# mc-v1-sch.net
KiCad netlist of a schematic drawn in EAGLE
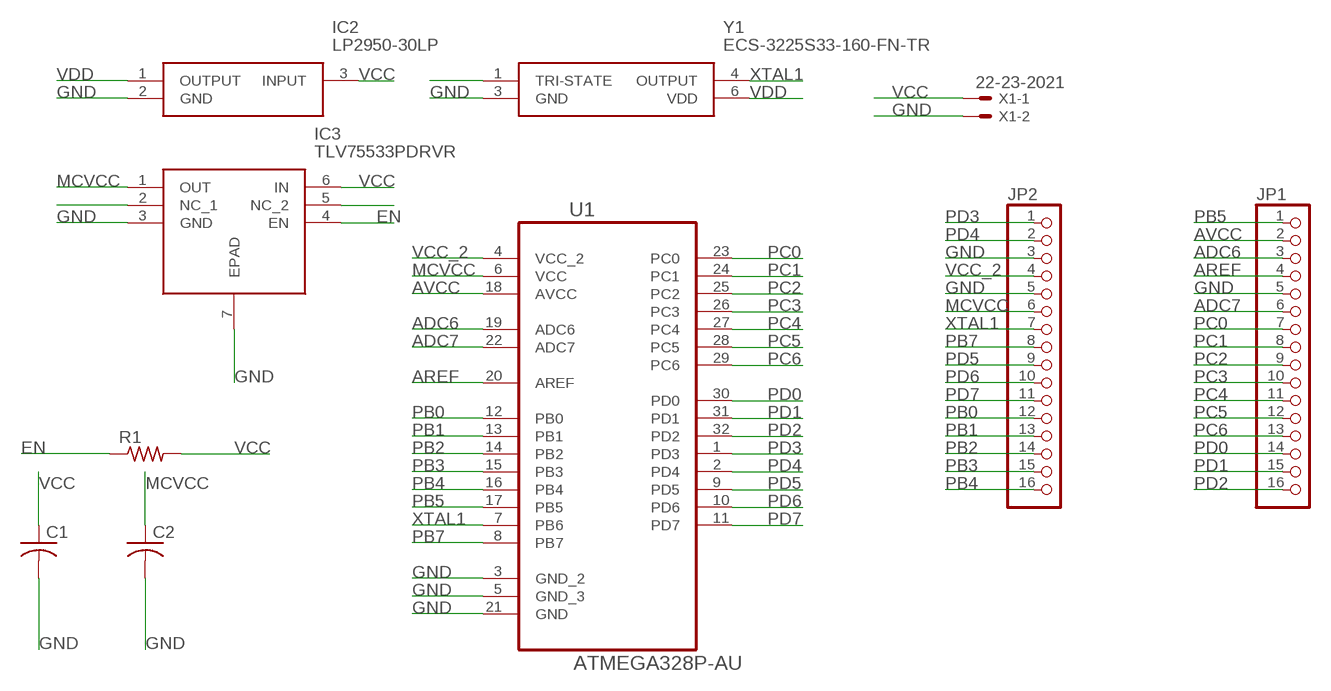
[diagram p0: schematic, sheet 1]

(export (version "E")
  (design (tool "Eeschema 10.0.6"))
  (components
    (comp (ref "C1")
      (value "C-USC1206")
      (footprint "eagle-import:C1206")
      (libsource (lib "eagle-import") (part "C-USC1206"))
    )
    (comp (ref "C2")
      (value "C-USC1206")
      (footprint "eagle-import:C1206")
      (libsource (lib "eagle-import") (part "C-USC1206"))
    )
    (comp (ref "IC2")
      (value "LP2950-30LP")
      (footprint "eagle-import:LP0003A")
      (fields (field (name "MOUSER_PART_NUMBER") "595-LP2950-30LP") (field (name "RS_PART_NUMBER") "7620437"))
      (libsource (lib "eagle-import") (part "LP2950-30LP"))
    )
    (comp (ref "IC3")
      (value "TLV75533PDRVR")
      (footprint "eagle-import:SON65P200X200X80-7N")
      (fields (field (name "MOUSER_PART_NUMBER") "595-TLV75533PDRVR"))
      (libsource (lib "eagle-import") (part "TLV75533PDRVR"))
    )
    (comp (ref "JP1")
      (value "PINHD-1X16")
      (footprint "eagle-import:1X16")
      (libsource (lib "eagle-import") (part "PINHD-1X16"))
    )
    (comp (ref "JP2")
      (value "PINHD-1X16")
      (footprint "eagle-import:1X16")
      (libsource (lib "eagle-import") (part "PINHD-1X16"))
    )
    (comp (ref "R1")
      (value "R-US_R0603")
      (footprint "eagle-import:R0603")
      (libsource (lib "eagle-import") (part "R-US_R0603"))
    )
    (comp (ref "U1")
      (value "ATMEGA328P-AU")
      (footprint "eagle-import:QFP80P900X900X120-32N")
      (libsource (lib "eagle-import") (part "ATMEGA328P-AU"))
    )
    (comp (ref "X1")
      (value "22-23-2021")
      (footprint "eagle-import:22-23-2021")
      (fields (field (name "MF") "MOLEX"))
      (libsource (lib "eagle-import") (part "22-23-2021"))
    )
    (comp (ref "Y1")
      (value "ECS-3225S33-160-FN-TR")
      (footprint "eagle-import:ECS3225S33200FNTR")
      (fields (field (name "MOUSER_PART_NUMBER") "520-3225S33-160-FNT"))
      (libsource (lib "eagle-import") (part "ECS-3225S33-160-FN-TR"))
    )
  )
  (nets
    (net (code "1") (name "/ADC6") (class "Default")
      (node (ref "JP1") (pin "3") (pinfunction "3_3") (pintype "passive"))
      (node (ref "U1") (pin "19") (pinfunction "ADC6_19") (pintype "input"))
    )
    (net (code "2") (name "/ADC7") (class "Default")
      (node (ref "JP1") (pin "6") (pinfunction "6_6") (pintype "passive"))
      (node (ref "U1") (pin "22") (pinfunction "ADC7_22") (pintype "input"))
    )
    (net (code "3") (name "/AREF") (class "Default")
      (node (ref "JP1") (pin "4") (pinfunction "4_4") (pintype "passive"))
      (node (ref "U1") (pin "20") (pinfunction "AREF_20") (pintype "input"))
    )
    (net (code "4") (name "/AVCC") (class "Default")
      (node (ref "JP1") (pin "2") (pinfunction "2_2") (pintype "passive"))
      (node (ref "U1") (pin "18") (pinfunction "AVCC_18") (pintype "power_in"))
    )
    (net (code "5") (name "/EN") (class "Default")
      (node (ref "IC3") (pin "4") (pinfunction "EN_4") (pintype "bidirectional"))
      (node (ref "R1") (pin "1") (pinfunction "1_1") (pintype "passive"))
    )
    (net (code "6") (name "/GND") (class "Default")
      (node (ref "C1") (pin "2") (pinfunction "2_2") (pintype "passive"))
      (node (ref "C2") (pin "2") (pinfunction "2_2") (pintype "passive"))
      (node (ref "IC2") (pin "2") (pinfunction "GND_2") (pintype "bidirectional"))
      (node (ref "IC3") (pin "3") (pinfunction "GND_3") (pintype "bidirectional"))
      (node (ref "IC3") (pin "7") (pinfunction "EPAD_7") (pintype "bidirectional"))
      (node (ref "JP1") (pin "5") (pinfunction "5_5") (pintype "passive"))
      (node (ref "JP2") (pin "3") (pinfunction "3_3") (pintype "passive"))
      (node (ref "JP2") (pin "5") (pinfunction "5_5") (pintype "passive"))
      (node (ref "U1") (pin "21") (pinfunction "GND_21") (pintype "passive"))
      (node (ref "U1") (pin "3") (pinfunction "GND_2_3") (pintype "passive"))
      (node (ref "U1") (pin "5") (pinfunction "GND_3_5") (pintype "passive"))
      (node (ref "X1") (pin "2") (pinfunction "S_2") (pintype "passive"))
      (node (ref "Y1") (pin "3") (pinfunction "GND_3") (pintype "bidirectional"))
    )
    (net (code "7") (name "/MCVCC") (class "Default")
      (node (ref "C2") (pin "1") (pinfunction "1_1") (pintype "passive"))
      (node (ref "IC3") (pin "1") (pinfunction "OUT_1") (pintype "bidirectional"))
      (node (ref "JP2") (pin "6") (pinfunction "6_6") (pintype "passive"))
      (node (ref "U1") (pin "6") (pinfunction "VCC_6") (pintype "power_in"))
    )
    (net (code "8") (name "/PB0") (class "Default")
      (node (ref "JP2") (pin "12") (pinfunction "12_12") (pintype "passive"))
      (node (ref "U1") (pin "12") (pinfunction "PB0_12") (pintype "bidirectional"))
    )
    (net (code "9") (name "/PB1") (class "Default")
      (node (ref "JP2") (pin "13") (pinfunction "13_13") (pintype "passive"))
      (node (ref "U1") (pin "13") (pinfunction "PB1_13") (pintype "bidirectional"))
    )
    (net (code "10") (name "/PB2") (class "Default")
      (node (ref "JP2") (pin "14") (pinfunction "14_14") (pintype "passive"))
      (node (ref "U1") (pin "14") (pinfunction "PB2_14") (pintype "bidirectional"))
    )
    (net (code "11") (name "/PB3") (class "Default")
      (node (ref "JP2") (pin "15") (pinfunction "15_15") (pintype "passive"))
      (node (ref "U1") (pin "15") (pinfunction "PB3_15") (pintype "bidirectional"))
    )
    (net (code "12") (name "/PB4") (class "Default")
      (node (ref "JP2") (pin "16") (pinfunction "16_16") (pintype "passive"))
      (node (ref "U1") (pin "16") (pinfunction "PB4_16") (pintype "bidirectional"))
    )
    (net (code "13") (name "/PB5") (class "Default")
      (node (ref "JP1") (pin "1") (pinfunction "1_1") (pintype "passive"))
      (node (ref "U1") (pin "17") (pinfunction "PB5_17") (pintype "bidirectional"))
    )
    (net (code "14") (name "/PB7") (class "Default")
      (node (ref "JP2") (pin "8") (pinfunction "8_8") (pintype "passive"))
      (node (ref "U1") (pin "8") (pinfunction "PB7_8") (pintype "bidirectional"))
    )
    (net (code "15") (name "/PC0") (class "Default")
      (node (ref "JP1") (pin "7") (pinfunction "7_7") (pintype "passive"))
      (node (ref "U1") (pin "23") (pinfunction "PC0_23") (pintype "bidirectional"))
    )
    (net (code "16") (name "/PC1") (class "Default")
      (node (ref "JP1") (pin "8") (pinfunction "8_8") (pintype "passive"))
      (node (ref "U1") (pin "24") (pinfunction "PC1_24") (pintype "bidirectional"))
    )
    (net (code "17") (name "/PC2") (class "Default")
      (node (ref "JP1") (pin "9") (pinfunction "9_9") (pintype "passive"))
      (node (ref "U1") (pin "25") (pinfunction "PC2_25") (pintype "bidirectional"))
    )
    (net (code "18") (name "/PC3") (class "Default")
      (node (ref "JP1") (pin "10") (pinfunction "10_10") (pintype "passive"))
      (node (ref "U1") (pin "26") (pinfunction "PC3_26") (pintype "bidirectional"))
    )
    (net (code "19") (name "/PC4") (class "Default")
      (node (ref "JP1") (pin "11") (pinfunction "11_11") (pintype "passive"))
      (node (ref "U1") (pin "27") (pinfunction "PC4_27") (pintype "bidirectional"))
    )
    (net (code "20") (name "/PC5") (class "Default")
      (node (ref "JP1") (pin "12") (pinfunction "12_12") (pintype "passive"))
      (node (ref "U1") (pin "28") (pinfunction "PC5_28") (pintype "bidirectional"))
    )
    (net (code "21") (name "/PC6") (class "Default")
      (node (ref "JP1") (pin "13") (pinfunction "13_13") (pintype "passive"))
      (node (ref "U1") (pin "29") (pinfunction "PC6_29") (pintype "bidirectional"))
    )
    (net (code "22") (name "/PD0") (class "Default")
      (node (ref "JP1") (pin "14") (pinfunction "14_14") (pintype "passive"))
      (node (ref "U1") (pin "30") (pinfunction "PD0_30") (pintype "bidirectional"))
    )
    (net (code "23") (name "/PD1") (class "Default")
      (node (ref "JP1") (pin "15") (pinfunction "15_15") (pintype "passive"))
      (node (ref "U1") (pin "31") (pinfunction "PD1_31") (pintype "bidirectional"))
    )
    (net (code "24") (name "/PD2") (class "Default")
      (node (ref "JP1") (pin "16") (pinfunction "16_16") (pintype "passive"))
      (node (ref "U1") (pin "32") (pinfunction "PD2_32") (pintype "bidirectional"))
    )
    (net (code "25") (name "/PD3") (class "Default")
      (node (ref "JP2") (pin "1") (pinfunction "1_1") (pintype "passive"))
      (node (ref "U1") (pin "1") (pinfunction "PD3_1") (pintype "bidirectional"))
    )
    (net (code "26") (name "/PD4") (class "Default")
      (node (ref "JP2") (pin "2") (pinfunction "2_2") (pintype "passive"))
      (node (ref "U1") (pin "2") (pinfunction "PD4_2") (pintype "bidirectional"))
    )
    (net (code "27") (name "/PD5") (class "Default")
      (node (ref "JP2") (pin "9") (pinfunction "9_9") (pintype "passive"))
      (node (ref "U1") (pin "9") (pinfunction "PD5_9") (pintype "bidirectional"))
    )
    (net (code "28") (name "/PD6") (class "Default")
      (node (ref "JP2") (pin "10") (pinfunction "10_10") (pintype "passive"))
      (node (ref "U1") (pin "10") (pinfunction "PD6_10") (pintype "bidirectional"))
    )
    (net (code "29") (name "/PD7") (class "Default")
      (node (ref "JP2") (pin "11") (pinfunction "11_11") (pintype "passive"))
      (node (ref "U1") (pin "11") (pinfunction "PD7_11") (pintype "bidirectional"))
    )
    (net (code "30") (name "/VCC") (class "Default")
      (node (ref "C1") (pin "1") (pinfunction "1_1") (pintype "passive"))
      (node (ref "IC2") (pin "3") (pinfunction "INPUT_3") (pintype "bidirectional"))
      (node (ref "IC3") (pin "6") (pinfunction "IN_6") (pintype "bidirectional"))
      (node (ref "R1") (pin "2") (pinfunction "2_2") (pintype "passive"))
      (node (ref "X1") (pin "1") (pinfunction "S_1") (pintype "passive"))
    )
    (net (code "31") (name "/VCC_2") (class "Default")
      (node (ref "JP2") (pin "4") (pinfunction "4_4") (pintype "passive"))
      (node (ref "U1") (pin "4") (pinfunction "VCC_2_4") (pintype "power_in"))
    )
    (net (code "32") (name "/VDD") (class "Default")
      (node (ref "IC2") (pin "1") (pinfunction "OUTPUT_1") (pintype "bidirectional"))
      (node (ref "Y1") (pin "6") (pinfunction "VDD_6") (pintype "bidirectional"))
    )
    (net (code "33") (name "/XTAL1") (class "Default")
      (node (ref "JP2") (pin "7") (pinfunction "7_7") (pintype "passive"))
      (node (ref "U1") (pin "7") (pinfunction "PB6_7") (pintype "bidirectional"))
      (node (ref "Y1") (pin "4") (pinfunction "OUTPUT_4") (pintype "bidirectional"))
    )
    (net (code "34") (name "unconnected-(IC3-NC_1-Pad2)") (class "Default")
      (node (ref "IC3") (pin "2") (pinfunction "NC_1_2") (pintype "bidirectional"))
    )
    (net (code "35") (name "unconnected-(IC3-NC_2-Pad5)") (class "Default")
      (node (ref "IC3") (pin "5") (pinfunction "NC_2_5") (pintype "bidirectional"))
    )
    (net (code "36") (name "unconnected-(Y1-TRI-STATE-Pad1)") (class "Default")
      (node (ref "Y1") (pin "1") (pinfunction "TRI-STATE_1") (pintype "bidirectional"))
    )
  )
)
